# Schematic.net
KiCad netlist of a schematic drawn in EAGLE
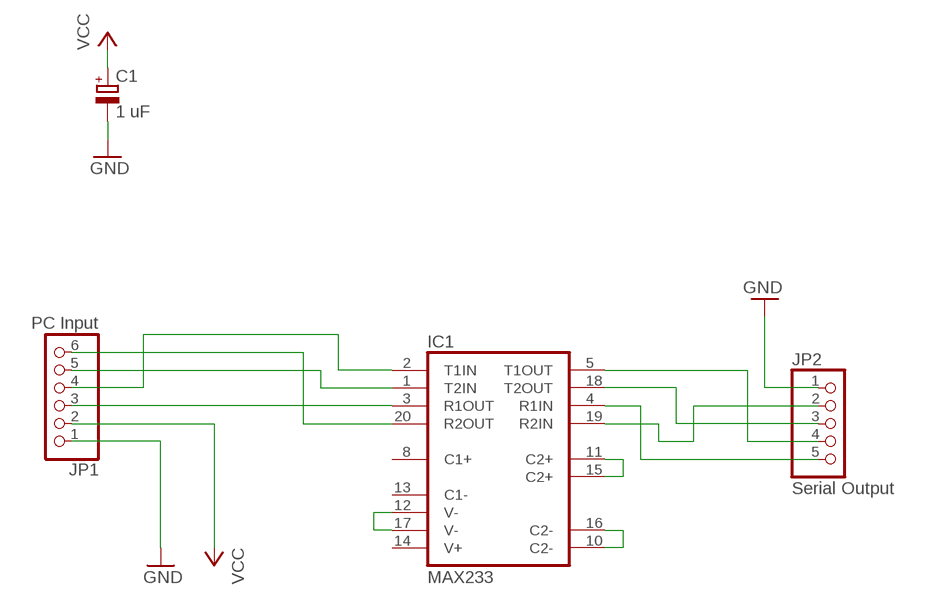
[diagram p0: schematic, sheet 1]

(export (version "E")
  (design (tool "Eeschema 10.0.6"))
  (components
    (comp (ref "C1")
      (value "1 uF")
      (footprint "eagle-import:E2,5-6")
      (libsource (lib "eagle-import") (part "CPOL-EUE2.5-6"))
    )
    (comp (ref "IC1")
      (value "MAX233")
      (footprint "eagle-import:DIL20")
      (fields (field (name "MPN") "MAX233ACPP+G36"))
      (libsource (lib "eagle-import") (part "MAX233"))
    )
    (comp (ref "JP1")
      (value "PC Input")
      (footprint "eagle-import:1X06")
      (libsource (lib "eagle-import") (part "PINHD-1X6"))
    )
    (comp (ref "JP2")
      (value "Serial Output")
      (footprint "eagle-import:1X05")
      (libsource (lib "eagle-import") (part "PINHD-1X5"))
    )
  )
  (nets
    (net (code "1") (name "GND") (class "Default")
      (node (ref "C1") (pin "-") (pinfunction "-_-") (pintype "passive"))
      (node (ref "JP1") (pin "1") (pinfunction "1_1") (pintype "passive"))
      (node (ref "JP2") (pin "1") (pinfunction "1_1") (pintype "passive"))
    )
    (net (code "2") (name "Net-(IC1A-C2+-Pad11)") (class "Default")
      (node (ref "IC1") (pin "11") (pinfunction "C2+_11") (pintype "bidirectional"))
      (node (ref "IC1") (pin "15") (pinfunction "C2+_15") (pintype "bidirectional"))
    )
    (net (code "3") (name "Net-(IC1A-C2--Pad10)") (class "Default")
      (node (ref "IC1") (pin "10") (pinfunction "C2-_10") (pintype "bidirectional"))
      (node (ref "IC1") (pin "16") (pinfunction "C2-_16") (pintype "bidirectional"))
    )
    (net (code "4") (name "Net-(IC1A-R1IN)") (class "Default")
      (node (ref "IC1") (pin "4") (pinfunction "R1IN_4") (pintype "input"))
      (node (ref "JP2") (pin "5") (pinfunction "5_5") (pintype "passive"))
    )
    (net (code "5") (name "Net-(IC1A-R1OUT)") (class "Default")
      (node (ref "IC1") (pin "3") (pinfunction "R1OUT_3") (pintype "output"))
      (node (ref "JP1") (pin "3") (pinfunction "3_3") (pintype "passive"))
    )
    (net (code "6") (name "Net-(IC1A-R2IN)") (class "Default")
      (node (ref "IC1") (pin "19") (pinfunction "R2IN_19") (pintype "input"))
      (node (ref "JP2") (pin "2") (pinfunction "2_2") (pintype "passive"))
    )
    (net (code "7") (name "Net-(IC1A-R2OUT)") (class "Default")
      (node (ref "IC1") (pin "20") (pinfunction "R2OUT_20") (pintype "output"))
      (node (ref "JP1") (pin "6") (pinfunction "6_6") (pintype "passive"))
    )
    (net (code "8") (name "Net-(IC1A-T1IN)") (class "Default")
      (node (ref "IC1") (pin "2") (pinfunction "T1IN_2") (pintype "input"))
      (node (ref "JP1") (pin "4") (pinfunction "4_4") (pintype "passive"))
    )
    (net (code "9") (name "Net-(IC1A-T1OUT)") (class "Default")
      (node (ref "IC1") (pin "5") (pinfunction "T1OUT_5") (pintype "output"))
      (node (ref "JP2") (pin "4") (pinfunction "4_4") (pintype "passive"))
    )
    (net (code "10") (name "Net-(IC1A-T2IN)") (class "Default")
      (node (ref "IC1") (pin "1") (pinfunction "T2IN_1") (pintype "input"))
      (node (ref "JP1") (pin "5") (pinfunction "5_5") (pintype "passive"))
    )
    (net (code "11") (name "Net-(IC1A-T2OUT)") (class "Default")
      (node (ref "IC1") (pin "18") (pinfunction "T2OUT_18") (pintype "output"))
      (node (ref "JP2") (pin "3") (pinfunction "3_3") (pintype "passive"))
    )
    (net (code "12") (name "Net-(IC1A-V--Pad12)") (class "Default")
      (node (ref "IC1") (pin "12") (pinfunction "V-_12") (pintype "bidirectional"))
      (node (ref "IC1") (pin "17") (pinfunction "V-_17") (pintype "bidirectional"))
    )
    (net (code "13") (name "VCC") (class "Default")
      (node (ref "C1") (pin "+") (pinfunction "+_+") (pintype "passive"))
      (node (ref "JP1") (pin "2") (pinfunction "2_2") (pintype "passive"))
    )
    (net (code "14") (name "unconnected-(IC1A-C1+-Pad8)") (class "Default")
      (node (ref "IC1") (pin "8") (pinfunction "C1+_8") (pintype "bidirectional"))
    )
    (net (code "15") (name "unconnected-(IC1A-C1--Pad13)") (class "Default")
      (node (ref "IC1") (pin "13") (pinfunction "C1-_13") (pintype "bidirectional"))
    )
    (net (code "16") (name "unconnected-(IC1A-V+-Pad14)") (class "Default")
      (node (ref "IC1") (pin "14") (pinfunction "V+_14") (pintype "bidirectional"))
    )
  )
)
